# driver_low_side.net
KiCad netlist of a schematic drawn in Altium Designer
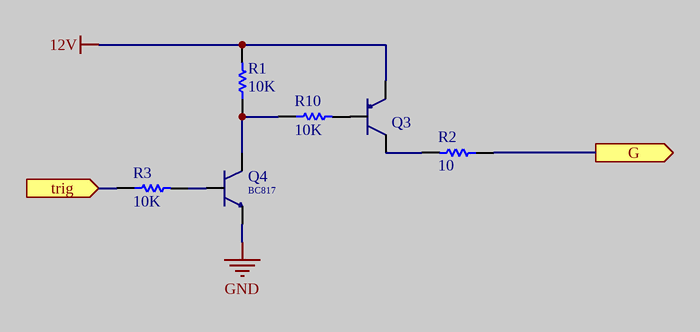
[diagram p0: driver_low_side.SchDoc]

(export (version "E")
  (design (tool "Eeschema 10.0.6"))
  (components
    (comp (ref "Q3")
      (value "PNP")
      (footprint "NPN")
      (description "45 V, 0.5 A")
      (libsource (lib "eLIB") (part "BC807"))
    )
    (comp (ref "Q4")
      (value "NPN transistor")
      (footprint "NPN")
      (description "45 V, 0.5 A")
      (fields (field (name "TRANSISTOR") "BC817"))
      (libsource (lib "eLIB") (part "BC817"))
    )
    (comp (ref "R1")
      (value "10K")
      (footprint "RESC0603")
      (description "0603,0.1W")
      (fields (field (name "PUBLISHER") "Altium Limited"))
      (libsource (lib "eLIB") (part "Resistor"))
    )
    (comp (ref "R2")
      (value "10")
      (footprint "RESC0603")
      (description "0603,0.1W")
      (fields (field (name "PUBLISHER") "Altium Limited"))
      (libsource (lib "eLIB") (part "Resistor"))
    )
    (comp (ref "R3")
      (value "10K")
      (footprint "RESC0603")
      (description "0603,0.1W")
      (fields (field (name "PUBLISHER") "Altium Limited"))
      (libsource (lib "eLIB") (part "Resistor"))
    )
    (comp (ref "R10")
      (value "10K")
      (footprint "RESC0603")
      (description "0603,0.1W")
      (fields (field (name "PUBLISHER") "Altium Limited"))
      (libsource (lib "eLIB") (part "Resistor"))
    )
  )
  (nets
    (net (code "1") (name "/G") (class "Default")
      (node (ref "R2") (pin "1") (pinfunction "1_1") (pintype "passive"))
    )
    (net (code "2") (name "/trig") (class "Default")
      (node (ref "R3") (pin "1") (pinfunction "1_1") (pintype "passive"))
    )
    (net (code "3") (name "12V") (class "Default")
      (node (ref "Q3") (pin "2") (pinfunction "E_2") (pintype "passive"))
      (node (ref "R1") (pin "2") (pinfunction "2_2") (pintype "passive"))
    )
    (net (code "4") (name "GND") (class "Default")
      (node (ref "Q4") (pin "2") (pinfunction "E_2") (pintype "passive"))
    )
    (net (code "5") (name "Net-(Q3-B)") (class "Default")
      (node (ref "Q3") (pin "1") (pinfunction "B_1") (pintype "passive"))
      (node (ref "R10") (pin "2") (pinfunction "2_2") (pintype "passive"))
    )
    (net (code "6") (name "Net-(Q3-C)") (class "Default")
      (node (ref "Q3") (pin "3") (pinfunction "C_3") (pintype "passive"))
      (node (ref "R2") (pin "2") (pinfunction "2_2") (pintype "passive"))
    )
    (net (code "7") (name "Net-(Q4-B)") (class "Default")
      (node (ref "Q4") (pin "1") (pinfunction "B_1") (pintype "passive"))
      (node (ref "R3") (pin "2") (pinfunction "2_2") (pintype "passive"))
    )
    (net (code "8") (name "Net-(Q4-C)") (class "Default")
      (node (ref "Q4") (pin "3") (pinfunction "C_3") (pintype "passive"))
      (node (ref "R1") (pin "1") (pinfunction "1_1") (pintype "passive"))
      (node (ref "R10") (pin "1") (pinfunction "1_1") (pintype "passive"))
    )
  )
)
